# v7-flex2811.net
KiCad netlist of a schematic drawn in EAGLE
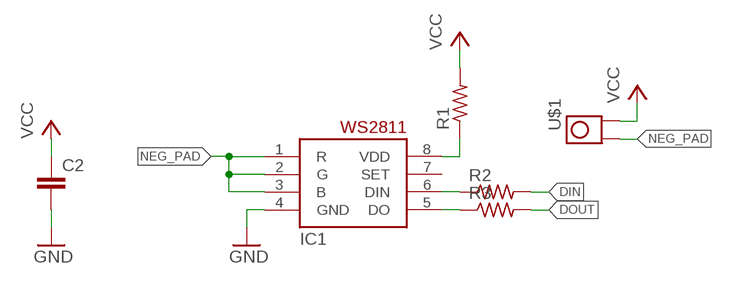
[diagram p0: schematic, sheet 1]

(export (version "E")
  (design (tool "Eeschema 10.0.6"))
  (components
    (comp (ref "C2")
      (value "C-EUC0402")
      (footprint "eagle-import:C0402")
      (libsource (lib "eagle-import") (part "C-EUC0402"))
    )
    (comp (ref "IC1")
      (value "WS2811-SOP8")
      (footprint "eagle-import:SO08-SKINNYPADS")
      (libsource (lib "eagle-import") (part "WS2811-SOP8"))
    )
    (comp (ref "R1")
      (value "R-US_R0402")
      (footprint "eagle-import:R0402")
      (libsource (lib "eagle-import") (part "R-US_R0402"))
    )
    (comp (ref "R2")
      (value "R-US_R0402")
      (footprint "eagle-import:R0402")
      (libsource (lib "eagle-import") (part "R-US_R0402"))
    )
    (comp (ref "R3")
      (value "R-US_R0402")
      (footprint "eagle-import:R0402")
      (libsource (lib "eagle-import") (part "R-US_R0402"))
    )
    (comp (ref "U$1")
      (value "TP_4MM_MED_PAD")
      (footprint "eagle-import:TP_4MM_MED_PAD")
      (libsource (lib "eagle-import") (part "TP_4MM_MED_PAD"))
    )
  )
  (nets
    (net (code "1") (name "DIN") (class "Default")
      (node (ref "R2") (pin "2") (pinfunction "2_2") (pintype "passive"))
    )
    (net (code "2") (name "DOUT") (class "Default")
      (node (ref "R3") (pin "2") (pinfunction "2_2") (pintype "passive"))
    )
    (net (code "3") (name "GND") (class "Default")
      (node (ref "C2") (pin "2") (pinfunction "2_2") (pintype "passive"))
      (node (ref "IC1") (pin "4") (pinfunction "GND_4") (pintype "power_in"))
    )
    (net (code "4") (name "NEG_PAD") (class "Default")
      (node (ref "IC1") (pin "1") (pinfunction "R_1") (pintype "open_collector"))
      (node (ref "IC1") (pin "2") (pinfunction "G_2") (pintype "open_collector"))
      (node (ref "IC1") (pin "3") (pinfunction "B_3") (pintype "open_collector"))
      (node (ref "U$1") (pin "P$1") (pinfunction "0_P$1") (pintype "bidirectional"))
    )
    (net (code "5") (name "Net-(IC1-DIN)") (class "Default")
      (node (ref "IC1") (pin "6") (pinfunction "DIN_6") (pintype "input"))
      (node (ref "R2") (pin "1") (pinfunction "1_1") (pintype "passive"))
    )
    (net (code "6") (name "Net-(IC1-DO)") (class "Default")
      (node (ref "IC1") (pin "5") (pinfunction "DO_5") (pintype "output"))
      (node (ref "R3") (pin "1") (pinfunction "1_1") (pintype "passive"))
    )
    (net (code "7") (name "Net-(IC1-VDD)") (class "Default")
      (node (ref "IC1") (pin "8") (pinfunction "VDD_8") (pintype "power_in"))
      (node (ref "R1") (pin "1") (pinfunction "1_1") (pintype "passive"))
    )
    (net (code "8") (name "VCC") (class "Default")
      (node (ref "C2") (pin "1") (pinfunction "1_1") (pintype "passive"))
      (node (ref "R1") (pin "2") (pinfunction "2_2") (pintype "passive"))
      (node (ref "U$1") (pin "P$2") (pinfunction "1_P$2") (pintype "bidirectional"))
    )
    (net (code "9") (name "unconnected-(IC1-SET-Pad7)") (class "Default")
      (node (ref "IC1") (pin "7") (pinfunction "SET_7") (pintype "input"))
    )
  )
)
